# FPV0_2_1.net
KiCad netlist of a schematic drawn in Altium Designer
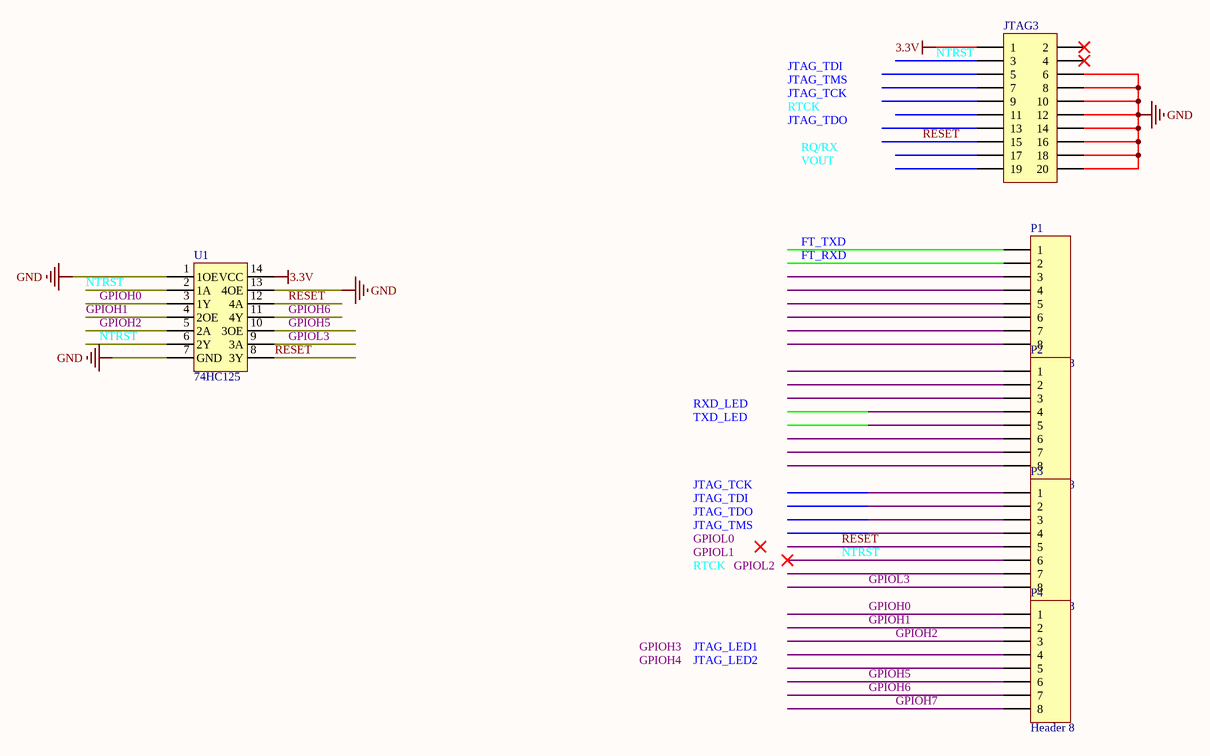
[diagram p0: FPV0.2.1.SchDoc]

(export (version "E")
  (design (tool "Eeschema 10.0.6"))
  (components
    (comp (ref "JTAG3")
      (value "Header 10X2")
      (footprint "HDR2X10")
      (description "Header, 10-Pin, Dual row")
      (fields (field (name "PUBLISHER") "Altium Limited"))
      (libsource (lib "Sparks") (part "Header 10X2"))
    )
    (comp (ref "P1")
      (value "Header 8")
      (footprint "HDR1X8")
      (description "Header, 8-Pin")
      (fields (field (name "PUBLISHER") "Altium Limited"))
      (libsource (lib "Sparks") (part "Header 8"))
    )
    (comp (ref "P2")
      (value "Header 8")
      (footprint "HDR1X8")
      (description "Header, 8-Pin")
      (fields (field (name "PUBLISHER") "Altium Limited"))
      (libsource (lib "Sparks") (part "Header 8"))
    )
    (comp (ref "P3")
      (value "Header 8")
      (footprint "HDR1X8")
      (description "Header, 8-Pin")
      (fields (field (name "PUBLISHER") "Altium Limited"))
      (libsource (lib "Sparks") (part "Header 8"))
    )
    (comp (ref "P4")
      (value "Header 8")
      (footprint "HDR1X8")
      (description "Header, 8-Pin")
      (fields (field (name "PUBLISHER") "Altium Limited"))
      (libsource (lib "Sparks") (part "Header 8"))
    )
    (comp (ref "U1")
      (value "74HC125")
      (footprint "SOP127P600-8N 74AHC125")
      (libsource (lib "2号库") (part "74HC126"))
    )
  )
  (nets
    (net (code "1") (name "/FT_RXD") (class "Default")
      (node (ref "P1") (pin "2") (pinfunction "2_2") (pintype "passive"))
    )
    (net (code "2") (name "/FT_TXD") (class "Default")
      (node (ref "P1") (pin "1") (pinfunction "1_1") (pintype "passive"))
    )
    (net (code "3") (name "/GPIOH0") (class "Default")
      (node (ref "P4") (pin "1") (pinfunction "1_1") (pintype "passive"))
      (node (ref "U1") (pin "3") (pinfunction "1Y_3") (pintype "passive"))
    )
    (net (code "4") (name "/GPIOH1") (class "Default")
      (node (ref "P4") (pin "2") (pinfunction "2_2") (pintype "passive"))
      (node (ref "U1") (pin "4") (pinfunction "2OE_4") (pintype "passive"))
    )
    (net (code "5") (name "/GPIOH2") (class "Default")
      (node (ref "P4") (pin "3") (pinfunction "3_3") (pintype "passive"))
      (node (ref "U1") (pin "5") (pinfunction "2A_5") (pintype "passive"))
    )
    (net (code "8") (name "/GPIOH5") (class "Default")
      (node (ref "P4") (pin "6") (pinfunction "6_6") (pintype "passive"))
      (node (ref "U1") (pin "10") (pinfunction "3OE_10") (pintype "passive"))
    )
    (net (code "9") (name "/GPIOH6") (class "Default")
      (node (ref "P4") (pin "7") (pinfunction "7_7") (pintype "passive"))
      (node (ref "U1") (pin "11") (pinfunction "4Y_11") (pintype "passive"))
    )
    (net (code "10") (name "/GPIOH7") (class "Default")
      (node (ref "P4") (pin "8") (pinfunction "8_8") (pintype "passive"))
    )
    (net (code "14") (name "/GPIOL3") (class "Default")
      (node (ref "P3") (pin "8") (pinfunction "8_8") (pintype "passive"))
      (node (ref "U1") (pin "9") (pinfunction "3A_9") (pintype "passive"))
    )
    (net (code "21") (name "/NTRST") (class "Default")
      (node (ref "JTAG3") (pin "3") (pinfunction "3_3") (pintype "passive"))
      (node (ref "P3") (pin "6") (pinfunction "6_6") (pintype "passive"))
      (node (ref "U1") (pin "2") (pinfunction "1A_2") (pintype "passive"))
      (node (ref "U1") (pin "6") (pinfunction "2Y_6") (pintype "passive"))
    )
    (net (code "22") (name "/RESET") (class "Default")
      (node (ref "JTAG3") (pin "15") (pinfunction "15_15") (pintype "passive"))
      (node (ref "P3") (pin "5") (pinfunction "5_5") (pintype "passive"))
      (node (ref "U1") (pin "12") (pinfunction "4A_12") (pintype "passive"))
      (node (ref "U1") (pin "8") (pinfunction "3Y_8") (pintype "passive"))
    )
    (net (code "28") (name "3.3V") (class "Default")
      (node (ref "JTAG3") (pin "1") (pinfunction "1_1") (pintype "passive"))
      (node (ref "U1") (pin "14") (pinfunction "VCC_14") (pintype "passive"))
    )
    (net (code "29") (name "GND") (class "Default")
      (node (ref "JTAG3") (pin "10") (pinfunction "10_10") (pintype "passive"))
      (node (ref "JTAG3") (pin "12") (pinfunction "12_12") (pintype "passive"))
      (node (ref "JTAG3") (pin "14") (pinfunction "14_14") (pintype "passive"))
      (node (ref "JTAG3") (pin "16") (pinfunction "16_16") (pintype "passive"))
      (node (ref "JTAG3") (pin "18") (pinfunction "18_18") (pintype "passive"))
      (node (ref "JTAG3") (pin "20") (pinfunction "20_20") (pintype "passive"))
      (node (ref "JTAG3") (pin "6") (pinfunction "6_6") (pintype "passive"))
      (node (ref "JTAG3") (pin "8") (pinfunction "8_8") (pintype "passive"))
      (node (ref "U1") (pin "1") (pinfunction "1OE_1") (pintype "passive"))
      (node (ref "U1") (pin "13") (pinfunction "4OE_13") (pintype "passive"))
      (node (ref "U1") (pin "7") (pinfunction "GND_7") (pintype "passive"))
    )
    (net (code "30") (name "unconnected-(JTAG3-Pad2)") (class "Default")
      (node (ref "JTAG3") (pin "2") (pinfunction "2_2") (pintype "passive+no_connect"))
    )
    (net (code "31") (name "unconnected-(JTAG3-Pad4)") (class "Default")
      (node (ref "JTAG3") (pin "4") (pinfunction "4_4") (pintype "passive+no_connect"))
    )
    (net (code "32") (name "unconnected-(JTAG3-Pad5)") (class "Default")
      (node (ref "JTAG3") (pin "5") (pinfunction "5_5") (pintype "passive"))
    )
    (net (code "33") (name "unconnected-(JTAG3-Pad7)") (class "Default")
      (node (ref "JTAG3") (pin "7") (pinfunction "7_7") (pintype "passive"))
    )
    (net (code "34") (name "unconnected-(JTAG3-Pad9)") (class "Default")
      (node (ref "JTAG3") (pin "9") (pinfunction "9_9") (pintype "passive"))
    )
    (net (code "35") (name "unconnected-(JTAG3-Pad11)") (class "Default")
      (node (ref "JTAG3") (pin "11") (pinfunction "11_11") (pintype "passive"))
    )
    (net (code "36") (name "unconnected-(JTAG3-Pad13)") (class "Default")
      (node (ref "JTAG3") (pin "13") (pinfunction "13_13") (pintype "passive"))
    )
    (net (code "37") (name "unconnected-(JTAG3-Pad17)") (class "Default")
      (node (ref "JTAG3") (pin "17") (pinfunction "17_17") (pintype "passive"))
    )
    (net (code "38") (name "unconnected-(JTAG3-Pad19)") (class "Default")
      (node (ref "JTAG3") (pin "19") (pinfunction "19_19") (pintype "passive"))
    )
    (net (code "39") (name "unconnected-(P1-Pad3)") (class "Default")
      (node (ref "P1") (pin "3") (pinfunction "3_3") (pintype "passive"))
    )
    (net (code "40") (name "unconnected-(P1-Pad4)") (class "Default")
      (node (ref "P1") (pin "4") (pinfunction "4_4") (pintype "passive"))
    )
    (net (code "41") (name "unconnected-(P1-Pad5)") (class "Default")
      (node (ref "P1") (pin "5") (pinfunction "5_5") (pintype "passive"))
    )
    (net (code "42") (name "unconnected-(P1-Pad6)") (class "Default")
      (node (ref "P1") (pin "6") (pinfunction "6_6") (pintype "passive"))
    )
    (net (code "43") (name "unconnected-(P1-Pad7)") (class "Default")
      (node (ref "P1") (pin "7") (pinfunction "7_7") (pintype "passive"))
    )
    (net (code "44") (name "unconnected-(P1-Pad8)") (class "Default")
      (node (ref "P1") (pin "8") (pinfunction "8_8") (pintype "passive"))
    )
    (net (code "45") (name "unconnected-(P2-Pad1)") (class "Default")
      (node (ref "P2") (pin "1") (pinfunction "1_1") (pintype "passive"))
    )
    (net (code "46") (name "unconnected-(P2-Pad2)") (class "Default")
      (node (ref "P2") (pin "2") (pinfunction "2_2") (pintype "passive"))
    )
    (net (code "47") (name "unconnected-(P2-Pad3)") (class "Default")
      (node (ref "P2") (pin "3") (pinfunction "3_3") (pintype "passive"))
    )
    (net (code "48") (name "unconnected-(P2-Pad4)") (class "Default")
      (node (ref "P2") (pin "4") (pinfunction "4_4") (pintype "passive"))
    )
    (net (code "49") (name "unconnected-(P2-Pad5)") (class "Default")
      (node (ref "P2") (pin "5") (pinfunction "5_5") (pintype "passive"))
    )
    (net (code "50") (name "unconnected-(P2-Pad6)") (class "Default")
      (node (ref "P2") (pin "6") (pinfunction "6_6") (pintype "passive"))
    )
    (net (code "51") (name "unconnected-(P2-Pad7)") (class "Default")
      (node (ref "P2") (pin "7") (pinfunction "7_7") (pintype "passive"))
    )
    (net (code "52") (name "unconnected-(P2-Pad8)") (class "Default")
      (node (ref "P2") (pin "8") (pinfunction "8_8") (pintype "passive"))
    )
    (net (code "53") (name "unconnected-(P3-Pad1)") (class "Default")
      (node (ref "P3") (pin "1") (pinfunction "1_1") (pintype "passive"))
    )
    (net (code "54") (name "unconnected-(P3-Pad2)") (class "Default")
      (node (ref "P3") (pin "2") (pinfunction "2_2") (pintype "passive"))
    )
    (net (code "55") (name "unconnected-(P3-Pad3)") (class "Default")
      (node (ref "P3") (pin "3") (pinfunction "3_3") (pintype "passive"))
    )
    (net (code "56") (name "unconnected-(P3-Pad4)") (class "Default")
      (node (ref "P3") (pin "4") (pinfunction "4_4") (pintype "passive"))
    )
    (net (code "57") (name "unconnected-(P3-Pad7)") (class "Default")
      (node (ref "P3") (pin "7") (pinfunction "7_7") (pintype "passive"))
    )
    (net (code "58") (name "unconnected-(P4-Pad4)") (class "Default")
      (node (ref "P4") (pin "4") (pinfunction "4_4") (pintype "passive"))
    )
    (net (code "59") (name "unconnected-(P4-Pad5)") (class "Default")
      (node (ref "P4") (pin "5") (pinfunction "5_5") (pintype "passive"))
    )
  )
)
